# Enclosure_100x68_PBC-AW.net
KiCad netlist of a schematic drawn in EAGLE
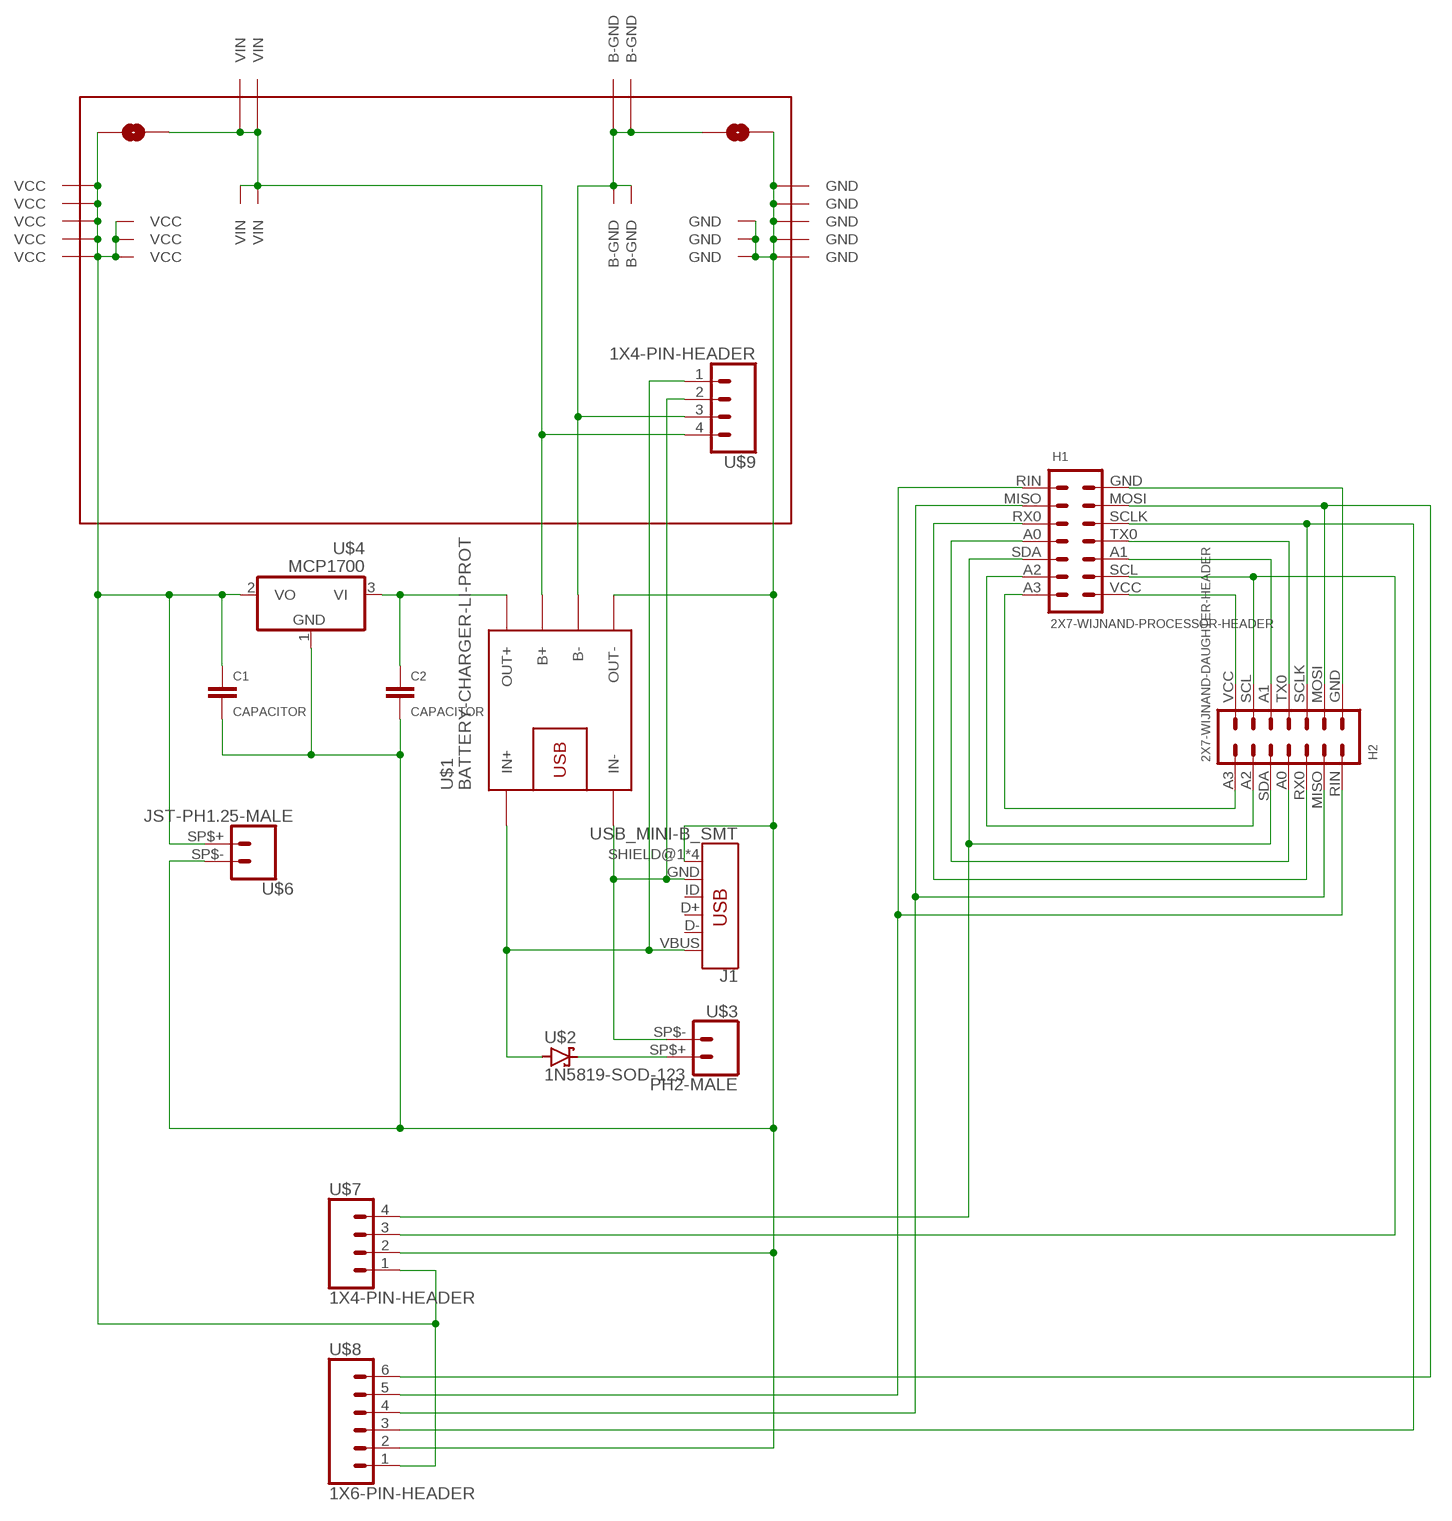
[diagram p0: schematic, sheet 1]

(export (version "E")
  (design (tool "Eeschema 10.0.6"))
  (components
    (comp (ref "C1")
      (value "CAPACITOR")
      (footprint "eagle-import:C0805")
      (libsource (lib "eagle-import") (part "CAPACITOR"))
    )
    (comp (ref "C2")
      (value "CAPACITOR")
      (footprint "eagle-import:C0805")
      (libsource (lib "eagle-import") (part "CAPACITOR"))
    )
    (comp (ref "H1")
      (value "2X7-WIJNAND-PROCESSOR-HEADER")
      (footprint "eagle-import:2X7-WIJNAND-PROCESSOR")
      (libsource (lib "eagle-import") (part "2X7-WIJNAND-PROCESSOR-HEADER"))
    )
    (comp (ref "H2")
      (value "2X7-WIJNAND-DAUGHTER-HEADER")
      (footprint "eagle-import:2X7-WIJNAND-DAUGHTER")
      (libsource (lib "eagle-import") (part "2X7-WIJNAND-DAUGHTER-HEADER"))
    )
    (comp (ref "J1")
      (value "USB_MINI-B_SMT")
      (footprint "eagle-import:USB-MINIB")
      (libsource (lib "eagle-import") (part "USB_MINI-B_SMT"))
    )
    (comp (ref "U$1")
      (value "BATTERY-CHARGER-LI-PROT")
      (footprint "eagle-import:BATTERY-CHARGER-LI-PROT")
      (libsource (lib "eagle-import") (part "BATTERY-CHARGER-LI-PROT"))
    )
    (comp (ref "U$2")
      (value "1N5819-SOD-123")
      (footprint "eagle-import:SOD-123")
      (libsource (lib "eagle-import") (part "1N5819-SOD-123"))
    )
    (comp (ref "U$3")
      (value "PH2-MALE")
      (footprint "eagle-import:PH2")
      (libsource (lib "eagle-import") (part "PH2-MALE"))
    )
    (comp (ref "U$4")
      (value "MCP1700")
      (footprint "eagle-import:SOT23")
      (libsource (lib "eagle-import") (part "MCP1700"))
    )
    (comp (ref "U$5")
      (value "PROTO-34X22-BAT-SJ-CHG-W")
      (footprint "eagle-import:PROTO-34X22-BAT-SJ-CHG-W")
      (libsource (lib "eagle-import") (part "PROTO-34X22-BAT-SJ-CHG-W"))
    )
    (comp (ref "U$6")
      (value "JST-PH1.25-MALE")
      (footprint "eagle-import:JST-PH1.25")
      (libsource (lib "eagle-import") (part "JST-PH1.25-MALE"))
    )
    (comp (ref "U$7")
      (value "1X4-PIN-HEADER")
      (footprint "eagle-import:CONN_04-GENERIC")
      (libsource (lib "eagle-import") (part "1X4-PIN-HEADER"))
    )
    (comp (ref "U$8")
      (value "1X6-PIN-HEADER")
      (footprint "eagle-import:CONN_06-GENERIC")
      (libsource (lib "eagle-import") (part "1X6-PIN-HEADER"))
    )
    (comp (ref "U$9")
      (value "1X4-PIN-HEADER")
      (footprint "eagle-import:CONN_04-GENERIC")
      (libsource (lib "eagle-import") (part "1X4-PIN-HEADER"))
    )
  )
  (nets
    (net (code "1") (name "Net-(H1-1)") (class "Default")
      (node (ref "H1") (pin "VCC") (pinfunction "1_VCC") (pintype "passive"))
      (node (ref "H2") (pin "VCC") (pinfunction "1_VCC") (pintype "passive"))
    )
    (net (code "2") (name "Net-(H1-2)") (class "Default")
      (node (ref "H1") (pin "SCL") (pinfunction "2_SCL") (pintype "passive"))
      (node (ref "H2") (pin "SCL") (pinfunction "2_SCL") (pintype "passive"))
      (node (ref "U$7") (pin "3") (pinfunction "3_3") (pintype "passive"))
    )
    (net (code "3") (name "Net-(H1-3)") (class "Default")
      (node (ref "H1") (pin "A1") (pinfunction "3_A1") (pintype "passive"))
      (node (ref "H2") (pin "A1") (pinfunction "3_A1") (pintype "passive"))
    )
    (net (code "4") (name "Net-(H1-4)") (class "Default")
      (node (ref "H1") (pin "TX0") (pinfunction "4_TX0") (pintype "passive"))
      (node (ref "H2") (pin "TX0") (pinfunction "4_TX0") (pintype "passive"))
    )
    (net (code "5") (name "Net-(H1-5)") (class "Default")
      (node (ref "H1") (pin "SCLK") (pinfunction "5_SCLK") (pintype "passive"))
      (node (ref "H2") (pin "SCLK") (pinfunction "5_SCLK") (pintype "passive"))
      (node (ref "U$8") (pin "3") (pinfunction "3_3") (pintype "passive"))
    )
    (net (code "6") (name "Net-(H1-6)") (class "Default")
      (node (ref "H1") (pin "MOSI") (pinfunction "6_MOSI") (pintype "passive"))
      (node (ref "H2") (pin "MOSI") (pinfunction "6_MOSI") (pintype "passive"))
      (node (ref "U$8") (pin "6") (pinfunction "6_6") (pintype "passive"))
    )
    (net (code "7") (name "Net-(H1-7)") (class "Default")
      (node (ref "H1") (pin "GND") (pinfunction "7_GND") (pintype "passive"))
      (node (ref "H2") (pin "GND") (pinfunction "7_GND") (pintype "passive"))
    )
    (net (code "8") (name "Net-(H1-8)") (class "Default")
      (node (ref "H1") (pin "RIN") (pinfunction "8_RIN") (pintype "passive"))
      (node (ref "H2") (pin "RIN") (pinfunction "8_RIN") (pintype "passive"))
      (node (ref "U$8") (pin "5") (pinfunction "5_5") (pintype "passive"))
    )
    (net (code "9") (name "Net-(H1-9)") (class "Default")
      (node (ref "H1") (pin "MISO") (pinfunction "9_MISO") (pintype "passive"))
      (node (ref "H2") (pin "MISO") (pinfunction "9_MISO") (pintype "passive"))
      (node (ref "U$8") (pin "4") (pinfunction "4_4") (pintype "passive"))
    )
    (net (code "10") (name "Net-(H1-10)") (class "Default")
      (node (ref "H1") (pin "RX0") (pinfunction "10_RX0") (pintype "passive"))
      (node (ref "H2") (pin "RX0") (pinfunction "10_RX0") (pintype "passive"))
    )
    (net (code "11") (name "Net-(H1-11)") (class "Default")
      (node (ref "H1") (pin "A0") (pinfunction "11_A0") (pintype "passive"))
      (node (ref "H2") (pin "A0") (pinfunction "11_A0") (pintype "passive"))
    )
    (net (code "12") (name "Net-(H1-12)") (class "Default")
      (node (ref "H1") (pin "SDA") (pinfunction "12_SDA") (pintype "passive"))
      (node (ref "H2") (pin "SDA") (pinfunction "12_SDA") (pintype "passive"))
      (node (ref "U$7") (pin "4") (pinfunction "4_4") (pintype "passive"))
    )
    (net (code "13") (name "Net-(H1-13)") (class "Default")
      (node (ref "H1") (pin "A2") (pinfunction "13_A2") (pintype "passive"))
      (node (ref "H2") (pin "A2") (pinfunction "13_A2") (pintype "passive"))
    )
    (net (code "14") (name "Net-(H1-14)") (class "Default")
      (node (ref "H1") (pin "A3") (pinfunction "14_A3") (pintype "passive"))
      (node (ref "H2") (pin "A3") (pinfunction "14_A3") (pintype "passive"))
    )
    (net (code "15") (name "Net-(U$1-PadB+)") (class "Default")
      (node (ref "U$1") (pin "B+") (pinfunction "B+_B+") (pintype "bidirectional"))
      (node (ref "U$5") (pin "P02-17") (pinfunction "VIN_P02-17") (pintype "power_in"))
      (node (ref "U$5") (pin "P03-16") (pinfunction "VIN_P03-16") (pintype "power_in"))
      (node (ref "U$5") (pin "P05-19") (pinfunction "VIN_P05-19") (pintype "power_in"))
      (node (ref "U$5") (pin "P06-19") (pinfunction "VIN_P06-19") (pintype "power_in"))
      (node (ref "U$5") (pin "VIN") (pinfunction "VIN_VIN") (pintype "power_in"))
      (node (ref "U$9") (pin "4") (pinfunction "4_4") (pintype "passive"))
    )
    (net (code "16") (name "Net-(U$1-PadB-)") (class "Default")
      (node (ref "U$1") (pin "B-") (pinfunction "B-_B-") (pintype "bidirectional"))
      (node (ref "U$5") (pin "B-GND") (pinfunction "B-GND_B-GND") (pintype "power_in"))
      (node (ref "U$5") (pin "P28-19") (pinfunction "B-GND_P28-19") (pintype "power_in"))
      (node (ref "U$5") (pin "P30-19") (pinfunction "B-GND_P30-19") (pintype "power_in"))
      (node (ref "U$5") (pin "P32-16") (pinfunction "B-GND_P32-16") (pintype "power_in"))
      (node (ref "U$5") (pin "P33-17") (pinfunction "B-GND_P33-17") (pintype "power_in"))
      (node (ref "U$9") (pin "3") (pinfunction "3_3") (pintype "passive"))
    )
    (net (code "17") (name "Net-(U$2-A)") (class "Default")
      (node (ref "J1") (pin "VBUS") (pinfunction "VBUS_VBUS") (pintype "power_in"))
      (node (ref "U$1") (pin "IN+") (pinfunction "IN+_IN+") (pintype "bidirectional"))
      (node (ref "U$2") (pin "1") (pinfunction "A_1") (pintype "passive"))
      (node (ref "U$9") (pin "1") (pinfunction "1_1") (pintype "passive"))
    )
    (net (code "18") (name "Net-(U$2-C)") (class "Default")
      (node (ref "U$2") (pin "2") (pinfunction "C_2") (pintype "passive"))
      (node (ref "U$3") (pin "SP$+") (pinfunction "1_SP$+") (pintype "power_in"))
    )
    (net (code "19") (name "Net-(U$3-2)") (class "Default")
      (node (ref "J1") (pin "GND") (pinfunction "GND_GND") (pintype "power_in"))
      (node (ref "U$1") (pin "IN-") (pinfunction "IN-_IN-") (pintype "bidirectional"))
      (node (ref "U$3") (pin "SP$-") (pinfunction "2_SP$-") (pintype "power_in"))
      (node (ref "U$9") (pin "2") (pinfunction "2_2") (pintype "passive"))
    )
    (net (code "20") (name "Net-(U$4-GND)") (class "Default")
      (node (ref "C1") (pin "2") (pinfunction "2_2") (pintype "passive"))
      (node (ref "C2") (pin "2") (pinfunction "2_2") (pintype "passive"))
      (node (ref "J1") (pin "SHIELD@1") (pinfunction "SHIELD_SHIELD@1") (pintype "power_in"))
      (node (ref "J1") (pin "SHIELD@2") (pinfunction "SHIELD_SHIELD@2") (pintype "power_in"))
      (node (ref "J1") (pin "SHIELD@3") (pinfunction "SHIELD_SHIELD@3") (pintype "power_in"))
      (node (ref "J1") (pin "SHIELD@4") (pinfunction "SHIELD_SHIELD@4") (pintype "power_in"))
      (node (ref "U$1") (pin "OUT-") (pinfunction "OUT-_OUT-") (pintype "bidirectional"))
      (node (ref "U$4") (pin "1") (pinfunction "GND_1") (pintype "passive"))
      (node (ref "U$5") (pin "GND") (pinfunction "GND_GND") (pintype "power_in"))
      (node (ref "U$5") (pin "P33-13") (pinfunction "GND_P33-13") (pintype "power_in"))
      (node (ref "U$5") (pin "P33-14") (pinfunction "GND_P33-14") (pintype "power_in"))
      (node (ref "U$5") (pin "P33-15") (pinfunction "GND_P33-15") (pintype "power_in"))
      (node (ref "U$5") (pin "P34-13") (pinfunction "GND_P34-13") (pintype "power_in"))
      (node (ref "U$5") (pin "P34-14") (pinfunction "GND_P34-14") (pintype "power_in"))
      (node (ref "U$5") (pin "P34-15") (pinfunction "GND_P34-15") (pintype "power_in"))
      (node (ref "U$5") (pin "P34-16") (pinfunction "GND_P34-16") (pintype "power_in"))
      (node (ref "U$5") (pin "P34-17") (pinfunction "GND_P34-17") (pintype "power_in"))
      (node (ref "U$6") (pin "SP$-") (pinfunction "2_SP$-") (pintype "power_in"))
      (node (ref "U$7") (pin "2") (pinfunction "2_2") (pintype "passive"))
      (node (ref "U$8") (pin "2") (pinfunction "2_2") (pintype "passive"))
    )
    (net (code "21") (name "Net-(U$4-VI)") (class "Default")
      (node (ref "C2") (pin "1") (pinfunction "1_1") (pintype "passive"))
      (node (ref "U$1") (pin "OUT+") (pinfunction "OUT+_OUT+") (pintype "bidirectional"))
      (node (ref "U$4") (pin "3") (pinfunction "VI_3") (pintype "input"))
    )
    (net (code "22") (name "Net-(U$4-VO)") (class "Default")
      (node (ref "C1") (pin "1") (pinfunction "1_1") (pintype "passive"))
      (node (ref "U$4") (pin "2") (pinfunction "VO_2") (pintype "output"))
      (node (ref "U$5") (pin "P01-13") (pinfunction "VCC_P01-13") (pintype "power_in"))
      (node (ref "U$5") (pin "P01-14") (pinfunction "VCC_P01-14") (pintype "power_in"))
      (node (ref "U$5") (pin "P01-15") (pinfunction "VCC_P01-15") (pintype "power_in"))
      (node (ref "U$5") (pin "P01-16") (pinfunction "VCC_P01-16") (pintype "power_in"))
      (node (ref "U$5") (pin "P01-17") (pinfunction "VCC_P01-17") (pintype "power_in"))
      (node (ref "U$5") (pin "P02-13") (pinfunction "VCC_P02-13") (pintype "power_in"))
      (node (ref "U$5") (pin "P02-14") (pinfunction "VCC_P02-14") (pintype "power_in"))
      (node (ref "U$5") (pin "P02-15") (pinfunction "VCC_P02-15") (pintype "power_in"))
      (node (ref "U$5") (pin "VCC") (pinfunction "VCC_VCC") (pintype "power_in"))
      (node (ref "U$6") (pin "SP$+") (pinfunction "1_SP$+") (pintype "power_in"))
      (node (ref "U$7") (pin "1") (pinfunction "1_1") (pintype "passive"))
      (node (ref "U$8") (pin "1") (pinfunction "1_1") (pintype "passive"))
    )
    (net (code "23") (name "unconnected-(J1-PadD+)") (class "Default")
      (node (ref "J1") (pin "D+") (pinfunction "D+_D+") (pintype "bidirectional"))
    )
    (net (code "24") (name "unconnected-(J1-PadD-)") (class "Default")
      (node (ref "J1") (pin "D-") (pinfunction "D-_D-") (pintype "bidirectional"))
    )
    (net (code "25") (name "unconnected-(J1-PadID)") (class "Default")
      (node (ref "J1") (pin "ID") (pinfunction "ID_ID") (pintype "bidirectional"))
    )
  )
)
